# XOR.net
KiCad netlist of a schematic drawn in EAGLE
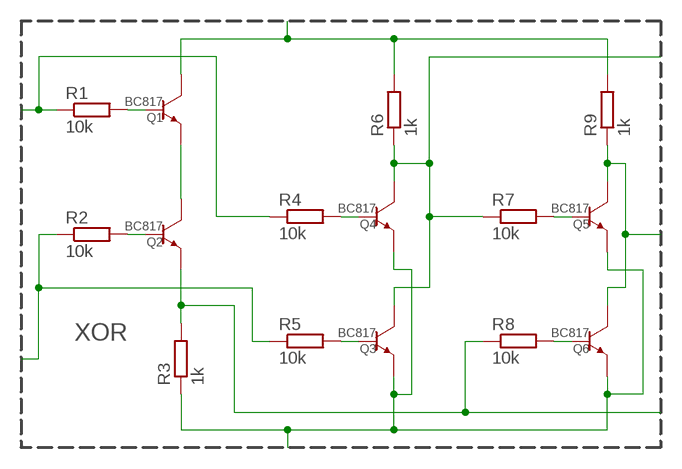
[diagram p0: schematic, sheet 1]

(export (version "E")
  (design (tool "Eeschema 10.0.6"))
  (components
    (comp (ref "Q1")
      (value "BC817")
      (footprint "eagle-import:SOT23")
      (libsource (lib "eagle-import") (part "TRANSISTOR-NPN-GENERIC-SOT23-BECDEFAULT"))
    )
    (comp (ref "Q2")
      (value "BC817")
      (footprint "eagle-import:SOT23")
      (libsource (lib "eagle-import") (part "TRANSISTOR-NPN-GENERIC-SOT23-BECDEFAULT"))
    )
    (comp (ref "Q3")
      (value "BC817")
      (footprint "eagle-import:SOT23")
      (libsource (lib "eagle-import") (part "TRANSISTOR-NPN-GENERIC-SOT23-BECDEFAULT"))
    )
    (comp (ref "Q4")
      (value "BC817")
      (footprint "eagle-import:SOT23")
      (libsource (lib "eagle-import") (part "TRANSISTOR-NPN-GENERIC-SOT23-BECDEFAULT"))
    )
    (comp (ref "Q5")
      (value "BC817")
      (footprint "eagle-import:SOT23")
      (libsource (lib "eagle-import") (part "TRANSISTOR-NPN-GENERIC-SOT23-BECDEFAULT"))
    )
    (comp (ref "Q6")
      (value "BC817")
      (footprint "eagle-import:SOT23")
      (libsource (lib "eagle-import") (part "TRANSISTOR-NPN-GENERIC-SOT23-BECDEFAULT"))
    )
    (comp (ref "R1")
      (value "10k")
      (footprint "eagle-import:R0603")
      (libsource (lib "eagle-import") (part "R-EU_R0603"))
    )
    (comp (ref "R2")
      (value "10k")
      (footprint "eagle-import:R0603")
      (libsource (lib "eagle-import") (part "R-EU_R0603"))
    )
    (comp (ref "R3")
      (value "1k")
      (footprint "eagle-import:R0603")
      (libsource (lib "eagle-import") (part "R-EU_R0603"))
    )
    (comp (ref "R4")
      (value "10k")
      (footprint "eagle-import:R0603")
      (libsource (lib "eagle-import") (part "R-EU_R0603"))
    )
    (comp (ref "R5")
      (value "10k")
      (footprint "eagle-import:R0603")
      (libsource (lib "eagle-import") (part "R-EU_R0603"))
    )
    (comp (ref "R6")
      (value "1k")
      (footprint "eagle-import:R0603")
      (libsource (lib "eagle-import") (part "R-EU_R0603"))
    )
    (comp (ref "R7")
      (value "10k")
      (footprint "eagle-import:R0603")
      (libsource (lib "eagle-import") (part "R-EU_R0603"))
    )
    (comp (ref "R8")
      (value "10k")
      (footprint "eagle-import:R0603")
      (libsource (lib "eagle-import") (part "R-EU_R0603"))
    )
    (comp (ref "R9")
      (value "1k")
      (footprint "eagle-import:R0603")
      (libsource (lib "eagle-import") (part "R-EU_R0603"))
    )
  )
  (nets
    (net (code "1") (name "Net-(Q1-BASE)") (class "Default")
      (node (ref "Q1") (pin "P$1") (pinfunction "BASE_P$1") (pintype "bidirectional"))
      (node (ref "R1") (pin "2") (pinfunction "2_2") (pintype "passive"))
    )
    (net (code "2") (name "Net-(Q1-COLLECTOR)") (class "Default")
      (node (ref "Q1") (pin "P$3") (pinfunction "COLLECTOR_P$3") (pintype "bidirectional"))
      (node (ref "R6") (pin "2") (pinfunction "2_2") (pintype "passive"))
      (node (ref "R9") (pin "2") (pinfunction "2_2") (pintype "passive"))
    )
    (net (code "3") (name "Net-(Q1-EMITTER)") (class "Default")
      (node (ref "Q1") (pin "P$2") (pinfunction "EMITTER_P$2") (pintype "bidirectional"))
      (node (ref "Q2") (pin "P$3") (pinfunction "COLLECTOR_P$3") (pintype "bidirectional"))
    )
    (net (code "4") (name "Net-(Q2-BASE)") (class "Default")
      (node (ref "Q2") (pin "P$1") (pinfunction "BASE_P$1") (pintype "bidirectional"))
      (node (ref "R2") (pin "2") (pinfunction "2_2") (pintype "passive"))
    )
    (net (code "5") (name "Net-(Q2-EMITTER)") (class "Default")
      (node (ref "Q2") (pin "P$2") (pinfunction "EMITTER_P$2") (pintype "bidirectional"))
      (node (ref "R3") (pin "2") (pinfunction "2_2") (pintype "passive"))
      (node (ref "R8") (pin "1") (pinfunction "1_1") (pintype "passive"))
    )
    (net (code "6") (name "Net-(Q3-BASE)") (class "Default")
      (node (ref "Q3") (pin "P$1") (pinfunction "BASE_P$1") (pintype "bidirectional"))
      (node (ref "R5") (pin "2") (pinfunction "2_2") (pintype "passive"))
    )
    (net (code "7") (name "Net-(Q3-COLLECTOR)") (class "Default")
      (node (ref "Q3") (pin "P$3") (pinfunction "COLLECTOR_P$3") (pintype "bidirectional"))
      (node (ref "Q4") (pin "P$3") (pinfunction "COLLECTOR_P$3") (pintype "bidirectional"))
      (node (ref "R6") (pin "1") (pinfunction "1_1") (pintype "passive"))
      (node (ref "R7") (pin "1") (pinfunction "1_1") (pintype "passive"))
    )
    (net (code "8") (name "Net-(Q3-EMITTER)") (class "Default")
      (node (ref "Q3") (pin "P$2") (pinfunction "EMITTER_P$2") (pintype "bidirectional"))
      (node (ref "Q4") (pin "P$2") (pinfunction "EMITTER_P$2") (pintype "bidirectional"))
      (node (ref "Q5") (pin "P$2") (pinfunction "EMITTER_P$2") (pintype "bidirectional"))
      (node (ref "Q6") (pin "P$2") (pinfunction "EMITTER_P$2") (pintype "bidirectional"))
      (node (ref "R3") (pin "1") (pinfunction "1_1") (pintype "passive"))
    )
    (net (code "9") (name "Net-(Q4-BASE)") (class "Default")
      (node (ref "Q4") (pin "P$1") (pinfunction "BASE_P$1") (pintype "bidirectional"))
      (node (ref "R4") (pin "2") (pinfunction "2_2") (pintype "passive"))
    )
    (net (code "10") (name "Net-(Q5-BASE)") (class "Default")
      (node (ref "Q5") (pin "P$1") (pinfunction "BASE_P$1") (pintype "bidirectional"))
      (node (ref "R7") (pin "2") (pinfunction "2_2") (pintype "passive"))
    )
    (net (code "11") (name "Net-(Q5-COLLECTOR)") (class "Default")
      (node (ref "Q5") (pin "P$3") (pinfunction "COLLECTOR_P$3") (pintype "bidirectional"))
      (node (ref "Q6") (pin "P$3") (pinfunction "COLLECTOR_P$3") (pintype "bidirectional"))
      (node (ref "R9") (pin "1") (pinfunction "1_1") (pintype "passive"))
    )
    (net (code "12") (name "Net-(Q6-BASE)") (class "Default")
      (node (ref "Q6") (pin "P$1") (pinfunction "BASE_P$1") (pintype "bidirectional"))
      (node (ref "R8") (pin "2") (pinfunction "2_2") (pintype "passive"))
    )
    (net (code "13") (name "Net-(R1-Pad1)") (class "Default")
      (node (ref "R1") (pin "1") (pinfunction "1_1") (pintype "passive"))
      (node (ref "R4") (pin "1") (pinfunction "1_1") (pintype "passive"))
    )
    (net (code "14") (name "Net-(R2-Pad1)") (class "Default")
      (node (ref "R2") (pin "1") (pinfunction "1_1") (pintype "passive"))
      (node (ref "R5") (pin "1") (pinfunction "1_1") (pintype "passive"))
    )
  )
)
